# UV_Sensor_Breakout_VEML6070_v1.net
KiCad netlist of a schematic drawn in EAGLE
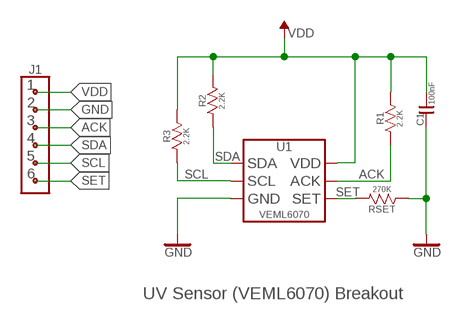
[diagram p0: schematic, sheet 1]

(export (version "E")
  (design (tool "Eeschema 10.0.6"))
  (components
    (comp (ref "C1")
      (value "100nF")
      (footprint "eagle-import:0603[1608]")
      (libsource (lib "eagle-import") (part "CAPACITOR_0603[1608]"))
    )
    (comp (ref "J1")
      (value "PIN_HEADER_1X06_0.1\"_STR_G[2]_PTH")
      (footprint "eagle-import:PIN_HEADER_1X06_0.1__STR_G[2]_PTH")
      (libsource (lib "eagle-import") (part "PIN_HEADER_1X06_0.1{dblquote}_STR_G[2]_PTH"))
    )
    (comp (ref "R1")
      (value "2.2K")
      (footprint "eagle-import:0603[1608]")
      (libsource (lib "eagle-import") (part "RESISTOR_0603[1008]"))
    )
    (comp (ref "R2")
      (value "2.2K")
      (footprint "eagle-import:0603[1608]")
      (libsource (lib "eagle-import") (part "RESISTOR_0603[1008]"))
    )
    (comp (ref "R3")
      (value "2.2K")
      (footprint "eagle-import:0603[1608]")
      (libsource (lib "eagle-import") (part "RESISTOR_0603[1008]"))
    )
    (comp (ref "RSET")
      (value "270K")
      (footprint "eagle-import:0603[1608]")
      (libsource (lib "eagle-import") (part "RESISTOR_0603[1008]"))
    )
    (comp (ref "U1")
      (value "VEML6070")
      (footprint "eagle-import:OPLGA")
      (libsource (lib "eagle-import") (part "UV_LIGHT_SENSOR_I2C_OPLGA"))
    )
  )
  (nets
    (net (code "1") (name "ACK") (class "Default")
      (node (ref "J1") (pin "3") (pinfunction "3_3") (pintype "bidirectional"))
      (node (ref "R1") (pin "1") (pinfunction "P1_1") (pintype "passive"))
      (node (ref "U1") (pin "2") (pinfunction "ACK_2") (pintype "bidirectional"))
    )
    (net (code "2") (name "GND") (class "Default")
      (node (ref "C1") (pin "1") (pinfunction "1_1") (pintype "passive"))
      (node (ref "J1") (pin "2") (pinfunction "2_2") (pintype "bidirectional"))
      (node (ref "RSET") (pin "1") (pinfunction "P1_1") (pintype "passive"))
      (node (ref "U1") (pin "1") (pinfunction "GND_1") (pintype "input"))
    )
    (net (code "3") (name "SCL") (class "Default")
      (node (ref "J1") (pin "5") (pinfunction "5_5") (pintype "bidirectional"))
      (node (ref "R3") (pin "1") (pinfunction "P1_1") (pintype "passive"))
      (node (ref "U1") (pin "5") (pinfunction "SCL_5") (pintype "input"))
    )
    (net (code "4") (name "SDA") (class "Default")
      (node (ref "J1") (pin "4") (pinfunction "4_4") (pintype "bidirectional"))
      (node (ref "R2") (pin "1") (pinfunction "P1_1") (pintype "passive"))
      (node (ref "U1") (pin "3") (pinfunction "SDA_3") (pintype "bidirectional"))
    )
    (net (code "5") (name "SET") (class "Default")
      (node (ref "J1") (pin "6") (pinfunction "6_6") (pintype "bidirectional"))
      (node (ref "RSET") (pin "2") (pinfunction "P2_2") (pintype "passive"))
      (node (ref "U1") (pin "4") (pinfunction "SET_4") (pintype "input"))
    )
    (net (code "6") (name "VDD") (class "Default")
      (node (ref "C1") (pin "2") (pinfunction "2_2") (pintype "passive"))
      (node (ref "J1") (pin "1") (pinfunction "1_1") (pintype "bidirectional"))
      (node (ref "R1") (pin "2") (pinfunction "P2_2") (pintype "passive"))
      (node (ref "R2") (pin "2") (pinfunction "P2_2") (pintype "passive"))
      (node (ref "R3") (pin "2") (pinfunction "P2_2") (pintype "passive"))
      (node (ref "U1") (pin "6") (pinfunction "VDD_6") (pintype "power_in"))
    )
  )
)
